# esquemacamiseta1bluetooth.net
KiCad netlist of a schematic drawn in EAGLE
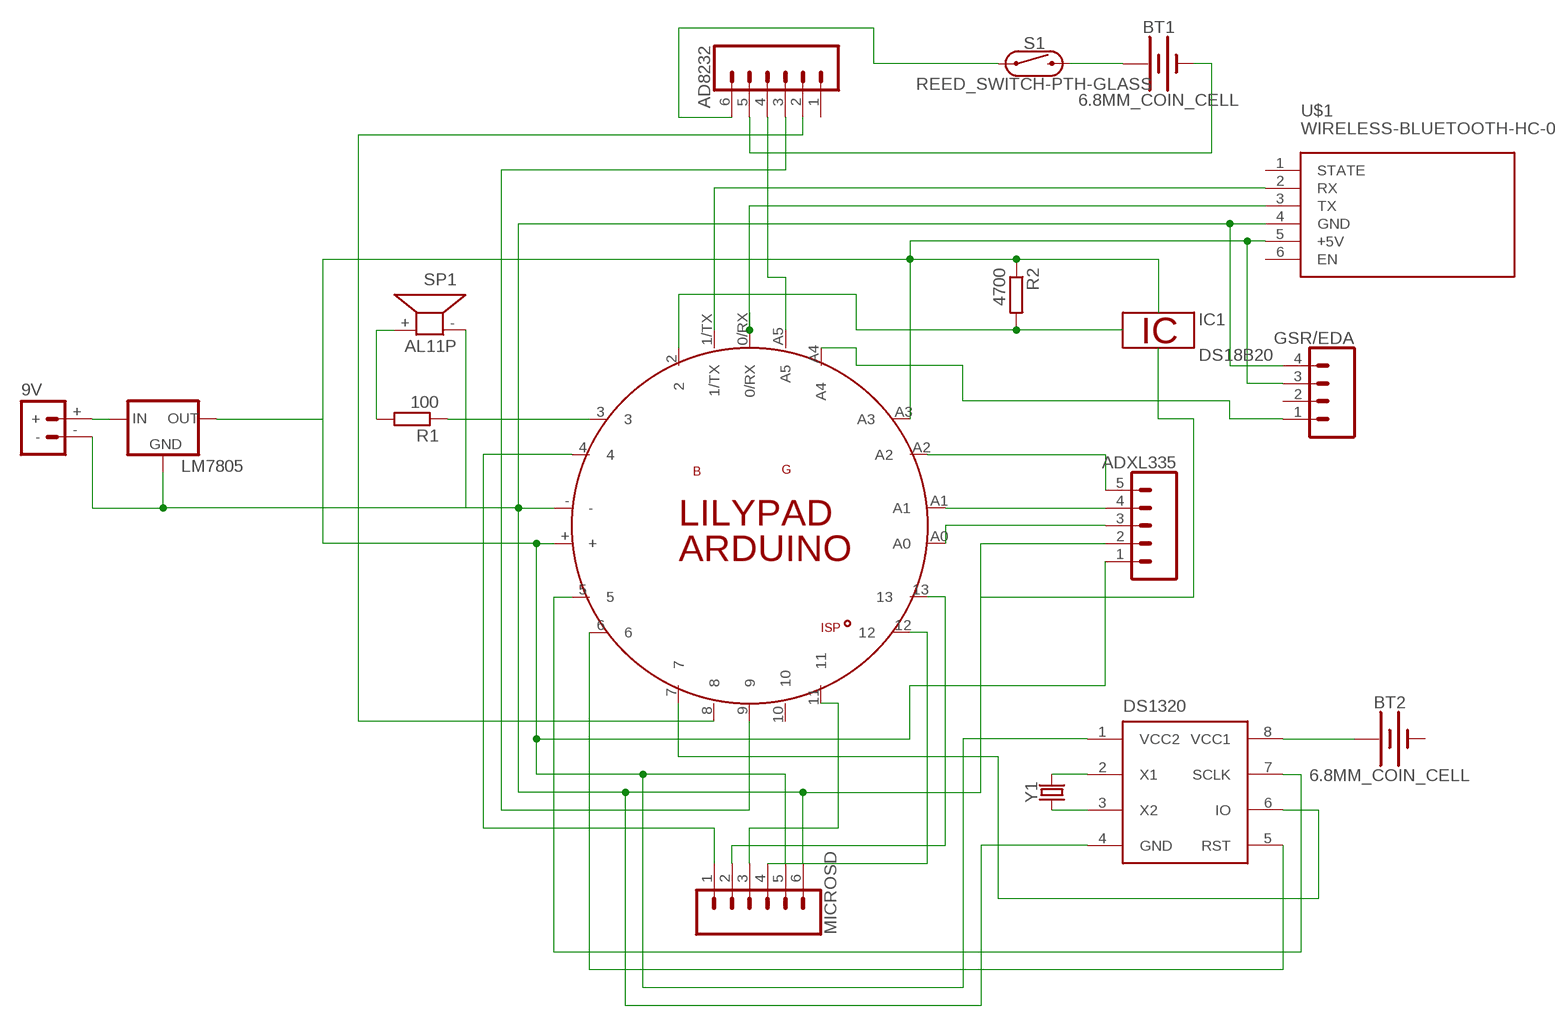
[diagram p0: schematic, sheet 1]

(export (version "E")
  (design (tool "Eeschema 10.0.6"))
  (components
    (comp (ref "9V")
      (value "BATTERY_CONN_DEANS")
      (footprint "eagle-import:DEANS")
      (libsource (lib "eagle-import") (part "BATTERY_CONN_DEANS"))
    )
    (comp (ref "AD8232")
      (value "CONN_06FEMALE_LOCK")
      (footprint "eagle-import:1X06_FEMALE_LOCK.010")
      (libsource (lib "eagle-import") (part "CONN_06FEMALE_LOCK"))
    )
    (comp (ref "ADXL335")
      (value "CONN_05")
      (footprint "eagle-import:1X05")
      (libsource (lib "eagle-import") (part "CONN_05"))
    )
    (comp (ref "BT1")
      (value "6.8MM_COIN_CELL")
      (footprint "eagle-import:BATTCON-6.8MM")
      (libsource (lib "eagle-import") (part "BATTERY-6.8MM_SMD"))
    )
    (comp (ref "BT2")
      (value "6.8MM_COIN_CELL")
      (footprint "eagle-import:BATTCON-6.8MM")
      (libsource (lib "eagle-import") (part "BATTERY-6.8MM_SMD"))
    )
    (comp (ref "DS1320")
      (value "DS1302")
      (footprint "eagle-import:PDIP8")
      (libsource (lib "eagle-import") (part "DS1302"))
    )
    (comp (ref "GSR/EDA")
      (value "CONN_04JST-PTH")
      (footprint "eagle-import:JST-4-PTH")
      (libsource (lib "eagle-import") (part "CONN_04JST-PTH"))
    )
    (comp (ref "IC1")
      (value "DS18B20")
      (footprint "eagle-import:TO92-")
      (libsource (lib "eagle-import") (part "DS18B20"))
    )
    (comp (ref "LM7805")
      (value "V_REG_78XX-TO-220")
      (footprint "eagle-import:TO-220-ALT")
      (libsource (lib "eagle-import") (part "V_REG_78XX-TO-220"))
    )
    (comp (ref "MICROSD")
      (value "CONN_06FEMALE_LOCK")
      (footprint "eagle-import:1X06_FEMALE_LOCK.010")
      (libsource (lib "eagle-import") (part "CONN_06FEMALE_LOCK"))
    )
    (comp (ref "PCB1")
      (value "ARDUINO_LILYPAD")
      (footprint "eagle-import:ARDUINO_LILYPAD")
      (libsource (lib "eagle-import") (part "ARDUINO_LILYPAD"))
    )
    (comp (ref "R1")
      (value "100")
      (footprint "eagle-import:0309_12")
      (libsource (lib "eagle-import") (part "R-EU_0309/12"))
    )
    (comp (ref "R2")
      (value "4700")
      (footprint "eagle-import:0309_12")
      (libsource (lib "eagle-import") (part "R-EU_0309/12"))
    )
    (comp (ref "S1")
      (value "REED_SWITCH-PTH-GLASS")
      (footprint "eagle-import:REED_SWITCH_GLASS")
      (libsource (lib "eagle-import") (part "REED_SWITCH-PTH-GLASS"))
    )
    (comp (ref "SP1")
      (value "AL11P")
      (footprint "eagle-import:AL11P")
      (libsource (lib "eagle-import") (part "AL11P"))
    )
    (comp (ref "U$1")
      (value "WIRELESS-BLUETOOTH-HC-05")
      (footprint "eagle-import:WIRELESS-BLUETOOTH-HC-05")
      (libsource (lib "eagle-import") (part "WIRELESS-BLUETOOTH-HC-05"))
    )
    (comp (ref "Y1")
      (value "CRYSTALPTH-2X6")
      (footprint "eagle-import:CRYSTAL-PTH-2X6-CYL")
      (libsource (lib "eagle-import") (part "CRYSTALPTH-2X6"))
    )
  )
  (nets
    (net (code "1") (name "/-") (class "Default")
      (node (ref "BT2") (pin "-") (pinfunction "-_-") (pintype "power_in"))
    )
    (net (code "2") (name "Net-(9V-Pad+)") (class "Default")
      (node (ref "9V") (pin "+") (pinfunction "+_+") (pintype "passive"))
      (node (ref "LM7805") (pin "IN") (pinfunction "IN_IN") (pintype "input"))
    )
    (net (code "3") (name "Net-(AD8232-Pad2)") (class "Default")
      (node (ref "AD8232") (pin "2") (pinfunction "2_2") (pintype "passive"))
      (node (ref "PCB1") (pin "8") (pinfunction "8_8") (pintype "bidirectional"))
    )
    (net (code "4") (name "Net-(AD8232-Pad3)") (class "Default")
      (node (ref "AD8232") (pin "3") (pinfunction "3_3") (pintype "passive"))
      (node (ref "PCB1") (pin "9") (pinfunction "9_9") (pintype "bidirectional"))
    )
    (net (code "5") (name "Net-(AD8232-Pad4)") (class "Default")
      (node (ref "AD8232") (pin "4") (pinfunction "4_4") (pintype "passive"))
      (node (ref "PCB1") (pin "A5") (pinfunction "A5_A5") (pintype "bidirectional"))
    )
    (net (code "6") (name "Net-(AD8232-Pad5)") (class "Default")
      (node (ref "AD8232") (pin "5") (pinfunction "5_5") (pintype "passive"))
      (node (ref "BT1") (pin "-") (pinfunction "-_-") (pintype "power_in"))
    )
    (net (code "7") (name "Net-(ADXL335-Pad3)") (class "Default")
      (node (ref "ADXL335") (pin "3") (pinfunction "3_3") (pintype "passive"))
      (node (ref "PCB1") (pin "A0") (pinfunction "A0_A0") (pintype "bidirectional"))
    )
    (net (code "8") (name "Net-(ADXL335-Pad4)") (class "Default")
      (node (ref "ADXL335") (pin "4") (pinfunction "4_4") (pintype "passive"))
      (node (ref "PCB1") (pin "A1") (pinfunction "A1_A1") (pintype "bidirectional"))
    )
    (net (code "9") (name "Net-(ADXL335-Pad5)") (class "Default")
      (node (ref "ADXL335") (pin "5") (pinfunction "5_5") (pintype "passive"))
      (node (ref "PCB1") (pin "A2") (pinfunction "A2_A2") (pintype "bidirectional"))
    )
    (net (code "10") (name "Net-(DS1320-GND)") (class "Default")
      (node (ref "9V") (pin "-") (pinfunction "-_-") (pintype "passive"))
      (node (ref "ADXL335") (pin "2") (pinfunction "2_2") (pintype "passive"))
      (node (ref "DS1320") (pin "4") (pinfunction "GND_4") (pintype "power_in"))
      (node (ref "GSR/EDA") (pin "4") (pinfunction "4_4") (pintype "passive"))
      (node (ref "LM7805") (pin "GND") (pinfunction "GND_GND") (pintype "input"))
      (node (ref "MICROSD") (pin "6") (pinfunction "6_6") (pintype "passive"))
      (node (ref "PCB1") (pin "-") (pinfunction "-_-") (pintype "bidirectional"))
      (node (ref "SP1") (pin "-") (pinfunction "1_-") (pintype "passive"))
      (node (ref "U$1") (pin "4") (pinfunction "GND_4") (pintype "power_in"))
    )
    (net (code "11") (name "Net-(DS1320-IO)") (class "Default")
      (node (ref "DS1320") (pin "6") (pinfunction "IO_6") (pintype "bidirectional"))
      (node (ref "PCB1") (pin "7") (pinfunction "7_7") (pintype "bidirectional"))
    )
    (net (code "12") (name "Net-(DS1320-RST)") (class "Default")
      (node (ref "DS1320") (pin "5") (pinfunction "RST_5") (pintype "input"))
      (node (ref "PCB1") (pin "6") (pinfunction "6_6") (pintype "bidirectional"))
    )
    (net (code "13") (name "Net-(DS1320-SCLK)") (class "Default")
      (node (ref "DS1320") (pin "7") (pinfunction "SCLK_7") (pintype "input"))
      (node (ref "PCB1") (pin "5") (pinfunction "5_5") (pintype "bidirectional"))
    )
    (net (code "14") (name "Net-(DS1320-VCC1)") (class "Default")
      (node (ref "BT2") (pin "+") (pinfunction "+_+") (pintype "power_in"))
      (node (ref "DS1320") (pin "8") (pinfunction "VCC1_8") (pintype "power_in"))
    )
    (net (code "15") (name "Net-(DS1320-VCC2)") (class "Default")
      (node (ref "ADXL335") (pin "1") (pinfunction "1_1") (pintype "passive"))
      (node (ref "DS1320") (pin "1") (pinfunction "VCC2_1") (pintype "power_in"))
      (node (ref "GSR/EDA") (pin "3") (pinfunction "3_3") (pintype "passive"))
      (node (ref "MICROSD") (pin "5") (pinfunction "5_5") (pintype "passive"))
      (node (ref "PCB1") (pin "+") (pinfunction "+_+") (pintype "bidirectional"))
      (node (ref "PCB1") (pin "A3") (pinfunction "A3_A3") (pintype "bidirectional"))
      (node (ref "R2") (pin "1") (pinfunction "1_1") (pintype "passive"))
      (node (ref "U$1") (pin "5") (pinfunction "+5V_5") (pintype "power_in"))
    )
    (net (code "16") (name "Net-(DS1320-X1)") (class "Default")
      (node (ref "DS1320") (pin "2") (pinfunction "X1_2") (pintype "bidirectional"))
      (node (ref "Y1") (pin "2") (pinfunction "2_2") (pintype "passive"))
    )
    (net (code "17") (name "Net-(DS1320-X2)") (class "Default")
      (node (ref "DS1320") (pin "3") (pinfunction "X2_3") (pintype "bidirectional"))
      (node (ref "Y1") (pin "1") (pinfunction "1_1") (pintype "passive"))
    )
    (net (code "18") (name "Net-(GSR/EDA-Pad1)") (class "Default")
      (node (ref "GSR/EDA") (pin "1") (pinfunction "1_1") (pintype "passive"))
      (node (ref "PCB1") (pin "A4") (pinfunction "A4_A4") (pintype "bidirectional"))
    )
    (net (code "19") (name "Net-(MICROSD-Pad1)") (class "Default")
      (node (ref "MICROSD") (pin "1") (pinfunction "1_1") (pintype "passive"))
      (node (ref "PCB1") (pin "4") (pinfunction "4_4") (pintype "bidirectional"))
    )
    (net (code "20") (name "Net-(MICROSD-Pad2)") (class "Default")
      (node (ref "MICROSD") (pin "2") (pinfunction "2_2") (pintype "passive"))
      (node (ref "PCB1") (pin "13") (pinfunction "13_13") (pintype "bidirectional"))
    )
    (net (code "21") (name "Net-(MICROSD-Pad3)") (class "Default")
      (node (ref "MICROSD") (pin "3") (pinfunction "3_3") (pintype "passive"))
      (node (ref "PCB1") (pin "11") (pinfunction "11_11") (pintype "bidirectional"))
    )
    (net (code "22") (name "Net-(MICROSD-Pad4)") (class "Default")
      (node (ref "MICROSD") (pin "4") (pinfunction "4_4") (pintype "passive"))
      (node (ref "PCB1") (pin "12") (pinfunction "12_12") (pintype "bidirectional"))
    )
    (net (code "23") (name "Net-(PCB1-Pad2)") (class "Default")
      (node (ref "PCB1") (pin "2") (pinfunction "2_2") (pintype "bidirectional"))
      (node (ref "R2") (pin "2") (pinfunction "2_2") (pintype "passive"))
    )
    (net (code "24") (name "Net-(PCB1-Pad3)") (class "Default")
      (node (ref "PCB1") (pin "3") (pinfunction "3_3") (pintype "bidirectional"))
      (node (ref "R1") (pin "1") (pinfunction "1_1") (pintype "passive"))
    )
    (net (code "25") (name "Net-(S1-1)") (class "Default")
      (node (ref "AD8232") (pin "6") (pinfunction "6_6") (pintype "passive"))
      (node (ref "S1") (pin "P$1") (pinfunction "1_P$1") (pintype "passive"))
    )
    (net (code "26") (name "Net-(S1-2)") (class "Default")
      (node (ref "BT1") (pin "+") (pinfunction "+_+") (pintype "power_in"))
      (node (ref "S1") (pin "P$2") (pinfunction "2_P$2") (pintype "passive"))
    )
    (net (code "27") (name "Net-(SP1-2)") (class "Default")
      (node (ref "R1") (pin "2") (pinfunction "2_2") (pintype "passive"))
      (node (ref "SP1") (pin "+") (pinfunction "2_+") (pintype "passive"))
    )
    (net (code "28") (name "Net-(U$1-RX)") (class "Default")
      (node (ref "PCB1") (pin "1/TX") (pinfunction "1/TX_1/TX") (pintype "bidirectional"))
      (node (ref "U$1") (pin "2") (pinfunction "RX_2") (pintype "bidirectional"))
    )
    (net (code "29") (name "Net-(U$1-TX)") (class "Default")
      (node (ref "PCB1") (pin "0/RX") (pinfunction "0/RX_0/RX") (pintype "bidirectional"))
      (node (ref "U$1") (pin "3") (pinfunction "TX_3") (pintype "bidirectional"))
    )
    (net (code "30") (name "unconnected-(AD8232-Pad1)") (class "Default")
      (node (ref "AD8232") (pin "1") (pinfunction "1_1") (pintype "passive"))
    )
    (net (code "31") (name "unconnected-(GSR/EDA-Pad2)") (class "Default")
      (node (ref "GSR/EDA") (pin "2") (pinfunction "2_2") (pintype "passive"))
    )
    (net (code "32") (name "unconnected-(LM7805-PadOUT)") (class "Default")
      (node (ref "LM7805") (pin "OUT") (pinfunction "OUT_OUT") (pintype "passive"))
    )
    (net (code "33") (name "unconnected-(PCB1-GND-PadGND_)") (class "Default")
      (node (ref "PCB1") (pin "GND_") (pinfunction "GND_GND_") (pintype "bidirectional"))
    )
    (net (code "34") (name "unconnected-(PCB1-Pad10)") (class "Default")
      (node (ref "PCB1") (pin "10") (pinfunction "10_10") (pintype "bidirectional"))
    )
    (net (code "35") (name "unconnected-(PCB1-PadDTR)") (class "Default")
      (node (ref "PCB1") (pin "DTR") (pinfunction "DTR_DTR") (pintype "bidirectional"))
    )
    (net (code "36") (name "unconnected-(PCB1-PadGND.)") (class "Default")
      (node (ref "PCB1") (pin "GND.") (pinfunction "GND._GND.") (pintype "bidirectional"))
    )
    (net (code "37") (name "unconnected-(PCB1-PadGND..)") (class "Default")
      (node (ref "PCB1") (pin "GND..") (pinfunction "GND.._GND..") (pintype "bidirectional"))
    )
    (net (code "38") (name "unconnected-(PCB1-PadMISO)") (class "Default")
      (node (ref "PCB1") (pin "MISO") (pinfunction "MISO_MISO") (pintype "bidirectional"))
    )
    (net (code "39") (name "unconnected-(PCB1-PadMOSI)") (class "Default")
      (node (ref "PCB1") (pin "MOSI") (pinfunction "MOSI_MOSI") (pintype "bidirectional"))
    )
    (net (code "40") (name "unconnected-(PCB1-PadRXI)") (class "Default")
      (node (ref "PCB1") (pin "RXI") (pinfunction "RXI_RXI") (pintype "bidirectional"))
    )
    (net (code "41") (name "unconnected-(PCB1-PadSCK)") (class "Default")
      (node (ref "PCB1") (pin "SCK") (pinfunction "SCK_SCK") (pintype "bidirectional"))
    )
    (net (code "42") (name "unconnected-(PCB1-PadTXO)") (class "Default")
      (node (ref "PCB1") (pin "TXO") (pinfunction "TXO_TXO") (pintype "bidirectional"))
    )
    (net (code "43") (name "unconnected-(PCB1-PadVCC.)") (class "Default")
      (node (ref "PCB1") (pin "VCC.") (pinfunction "VCC._VCC.") (pintype "bidirectional"))
    )
    (net (code "44") (name "unconnected-(PCB1-RST-PadRESET..)") (class "Default")
      (node (ref "PCB1") (pin "RESET..") (pinfunction "RST_RESET..") (pintype "bidirectional"))
    )
    (net (code "45") (name "unconnected-(PCB1-VCC-Pad5V.)") (class "Default")
      (node (ref "PCB1") (pin "5V.") (pinfunction "VCC_5V.") (pintype "bidirectional"))
    )
    (net (code "46") (name "unconnected-(U$1-EN-Pad6)") (class "Default")
      (node (ref "U$1") (pin "6") (pinfunction "EN_6") (pintype "bidirectional"))
    )
    (net (code "47") (name "unconnected-(U$1-STATE-Pad1)") (class "Default")
      (node (ref "U$1") (pin "1") (pinfunction "STATE_1") (pintype "bidirectional"))
    )
  )
)
